# interface.net
KiCad netlist of a schematic drawn in Altium Designer
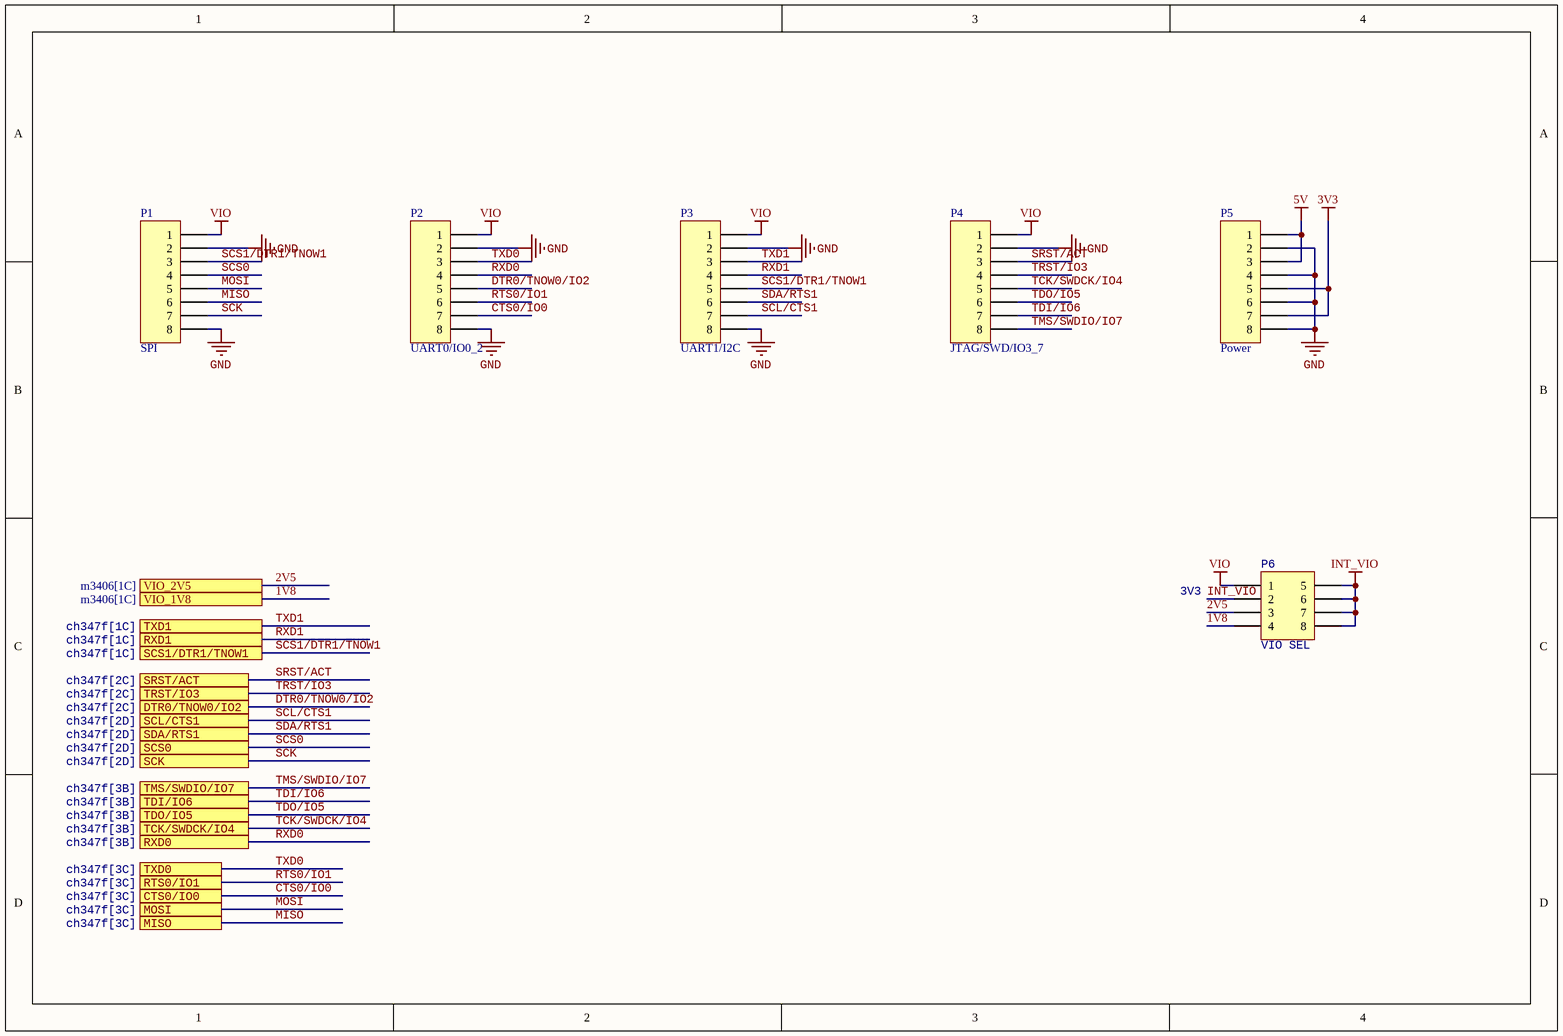
[diagram p0: interface.SchDoc]

(export (version "E")
  (design (tool "Eeschema 10.0.6"))
  (components
    (comp (ref "P1")
      (value "SPI")
      (footprint "ch347-hs-usb-bridge:CONN-SMD_PH2.0-8P-LT")
      (description "Header, 8-Pin")
      (fields (field (name "PUBLISHER") "Altium Limited"))
      (libsource (lib "Miscellaneous Connectors") (part "Header 8"))
    )
    (comp (ref "P2")
      (value "UART0/IO0_2")
      (footprint "ch347-hs-usb-bridge:CONN-SMD_PH2.0-8P-LT")
      (description "Header, 8-Pin")
      (fields (field (name "PUBLISHER") "Altium Limited"))
      (libsource (lib "Miscellaneous Connectors") (part "Header 8"))
    )
    (comp (ref "P3")
      (value "UART1/I2C")
      (footprint "ch347-hs-usb-bridge:CONN-SMD_PH2.0-8P-LT")
      (description "Header, 8-Pin")
      (fields (field (name "PUBLISHER") "Altium Limited"))
      (libsource (lib "Miscellaneous Connectors") (part "Header 8"))
    )
    (comp (ref "P4")
      (value "JTAG/SWD/IO3_7")
      (footprint "ch347-hs-usb-bridge:CONN-SMD_PH2.0-8P-LT")
      (description "Header, 8-Pin")
      (fields (field (name "PUBLISHER") "Altium Limited"))
      (libsource (lib "Miscellaneous Connectors") (part "Header 8"))
    )
    (comp (ref "P5")
      (value "Power")
      (footprint "ch347-hs-usb-bridge:CONN-SMD_PH2.0-8P-LT")
      (description "Header, 8-Pin")
      (fields (field (name "PUBLISHER") "Altium Limited"))
      (libsource (lib "Miscellaneous Connectors") (part "Header 8"))
    )
    (comp (ref "P6")
      (value "VIO SEL")
      (footprint "ch347-hs-usb-bridge:CONN-SMD_HX-PZ2.0-2X4P-TP")
      (description "Header, 4-Pin, Dual row")
      (fields (field (name "PUBLISHER") "Altium Limited"))
      (libsource (lib "Miscellaneous Connectors") (part "Header 4X2A"))
    )
  )
  (nets
    (net (code "1") (name "/1V8") (class "Default")
      (node (ref "P6") (pin "4") (pinfunction "4_4") (pintype "passive"))
    )
    (net (code "2") (name "/2V5") (class "Default")
      (node (ref "P6") (pin "3") (pinfunction "3_3") (pintype "passive"))
    )
    (net (code "3") (name "/CTS0{slash}IO0") (class "Default")
      (node (ref "P2") (pin "7") (pinfunction "7_7") (pintype "passive"))
    )
    (net (code "4") (name "/DTR0{slash}TNOW0{slash}IO2") (class "Default")
      (node (ref "P2") (pin "5") (pinfunction "5_5") (pintype "passive"))
    )
    (net (code "5") (name "/MISO") (class "Default")
      (node (ref "P1") (pin "6") (pinfunction "6_6") (pintype "passive"))
    )
    (net (code "6") (name "/MOSI") (class "Default")
      (node (ref "P1") (pin "5") (pinfunction "5_5") (pintype "passive"))
    )
    (net (code "7") (name "/RTS0{slash}IO1") (class "Default")
      (node (ref "P2") (pin "6") (pinfunction "6_6") (pintype "passive"))
    )
    (net (code "8") (name "/RXD0") (class "Default")
      (node (ref "P2") (pin "4") (pinfunction "4_4") (pintype "passive"))
    )
    (net (code "9") (name "/RXD1") (class "Default")
      (node (ref "P3") (pin "4") (pinfunction "4_4") (pintype "passive"))
    )
    (net (code "10") (name "/SCK") (class "Default")
      (node (ref "P1") (pin "7") (pinfunction "7_7") (pintype "passive"))
    )
    (net (code "11") (name "/SCL{slash}CTS1") (class "Default")
      (node (ref "P3") (pin "7") (pinfunction "7_7") (pintype "passive"))
    )
    (net (code "12") (name "/SCS0") (class "Default")
      (node (ref "P1") (pin "4") (pinfunction "4_4") (pintype "passive"))
    )
    (net (code "13") (name "/SCS1{slash}DTR1{slash}TNOW1") (class "Default")
      (node (ref "P1") (pin "3") (pinfunction "3_3") (pintype "passive"))
      (node (ref "P3") (pin "5") (pinfunction "5_5") (pintype "passive"))
    )
    (net (code "14") (name "/SDA{slash}RTS1") (class "Default")
      (node (ref "P3") (pin "6") (pinfunction "6_6") (pintype "passive"))
    )
    (net (code "15") (name "/SRST{slash}ACT") (class "Default")
      (node (ref "P4") (pin "3") (pinfunction "3_3") (pintype "passive"))
    )
    (net (code "16") (name "/TCK{slash}SWDCK{slash}IO4") (class "Default")
      (node (ref "P4") (pin "5") (pinfunction "5_5") (pintype "passive"))
    )
    (net (code "17") (name "/TDI{slash}IO6") (class "Default")
      (node (ref "P4") (pin "7") (pinfunction "7_7") (pintype "passive"))
    )
    (net (code "18") (name "/TDO{slash}IO5") (class "Default")
      (node (ref "P4") (pin "6") (pinfunction "6_6") (pintype "passive"))
    )
    (net (code "19") (name "/TMS{slash}SWDIO{slash}IO7") (class "Default")
      (node (ref "P4") (pin "8") (pinfunction "8_8") (pintype "passive"))
    )
    (net (code "20") (name "/TRST{slash}IO3") (class "Default")
      (node (ref "P4") (pin "4") (pinfunction "4_4") (pintype "passive"))
    )
    (net (code "21") (name "/TXD0") (class "Default")
      (node (ref "P2") (pin "3") (pinfunction "3_3") (pintype "passive"))
    )
    (net (code "22") (name "/TXD1") (class "Default")
      (node (ref "P3") (pin "3") (pinfunction "3_3") (pintype "passive"))
    )
    (net (code "23") (name "3V3") (class "Default")
      (node (ref "P5") (pin "5") (pinfunction "5_5") (pintype "passive"))
      (node (ref "P5") (pin "7") (pinfunction "7_7") (pintype "passive"))
    )
    (net (code "24") (name "5V") (class "Default")
      (node (ref "P5") (pin "1") (pinfunction "1_1") (pintype "passive"))
      (node (ref "P5") (pin "3") (pinfunction "3_3") (pintype "passive"))
    )
    (net (code "25") (name "GND") (class "Default")
      (node (ref "P1") (pin "2") (pinfunction "2_2") (pintype "passive"))
      (node (ref "P1") (pin "8") (pinfunction "8_8") (pintype "passive"))
      (node (ref "P2") (pin "2") (pinfunction "2_2") (pintype "passive"))
      (node (ref "P2") (pin "8") (pinfunction "8_8") (pintype "passive"))
      (node (ref "P3") (pin "2") (pinfunction "2_2") (pintype "passive"))
      (node (ref "P3") (pin "8") (pinfunction "8_8") (pintype "passive"))
      (node (ref "P4") (pin "2") (pinfunction "2_2") (pintype "passive"))
      (node (ref "P5") (pin "2") (pinfunction "2_2") (pintype "passive"))
      (node (ref "P5") (pin "4") (pinfunction "4_4") (pintype "passive"))
      (node (ref "P5") (pin "6") (pinfunction "6_6") (pintype "passive"))
      (node (ref "P5") (pin "8") (pinfunction "8_8") (pintype "passive"))
    )
    (net (code "26") (name "INT_VIO") (class "Default")
      (node (ref "P6") (pin "2") (pinfunction "2_2") (pintype "passive"))
      (node (ref "P6") (pin "5") (pinfunction "5_5") (pintype "passive"))
      (node (ref "P6") (pin "6") (pinfunction "6_6") (pintype "passive"))
      (node (ref "P6") (pin "7") (pinfunction "7_7") (pintype "passive"))
      (node (ref "P6") (pin "8") (pinfunction "8_8") (pintype "passive"))
    )
    (net (code "27") (name "VIO") (class "Default")
      (node (ref "P1") (pin "1") (pinfunction "1_1") (pintype "passive"))
      (node (ref "P2") (pin "1") (pinfunction "1_1") (pintype "passive"))
      (node (ref "P3") (pin "1") (pinfunction "1_1") (pintype "passive"))
      (node (ref "P4") (pin "1") (pinfunction "1_1") (pintype "passive"))
      (node (ref "P6") (pin "1") (pinfunction "1_1") (pintype "passive"))
    )
  )
)
